# Sheet1.net
KiCad netlist of a schematic drawn in Altium Designer
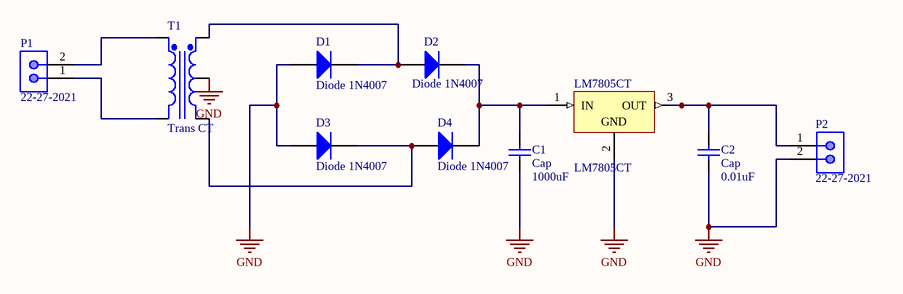
[diagram p0: Sheet1.SchDoc]

(export (version "E")
  (design (tool "Eeschema 10.0.6"))
  (components
    (comp (ref "C1")
      (value "Cap")
      (footprint "RAD-0.3")
      (description "Capacitor")
      (fields (field (name "ALTIUM_VALUE") "1000uF") (field (name "PUBLISHER") "Altium Limited"))
      (libsource (lib "Miscellaneous Devices") (part "Cap"))
    )
    (comp (ref "C2")
      (value "Cap")
      (footprint "RAD-0.3")
      (description "Capacitor")
      (fields (field (name "ALTIUM_VALUE") "0.01uF") (field (name "PUBLISHER") "Altium Limited"))
      (libsource (lib "Miscellaneous Devices") (part "Cap"))
    )
    (comp (ref "D1")
      (value "Diode 1N4007")
      (footprint "DO-41")
      (description "1 Amp General Purpose Rectifier")
      (fields (field (name "PUBLISHER") "Altium Limited"))
      (libsource (lib "Miscellaneous Devices") (part "Diode 1N4007"))
    )
    (comp (ref "D2")
      (value "Diode 1N4007")
      (footprint "DO-41")
      (description "1 Amp General Purpose Rectifier")
      (fields (field (name "PUBLISHER") "Altium Limited"))
      (libsource (lib "Miscellaneous Devices") (part "Diode 1N4007"))
    )
    (comp (ref "D3")
      (value "Diode 1N4007")
      (footprint "DO-41")
      (description "1 Amp General Purpose Rectifier")
      (fields (field (name "PUBLISHER") "Altium Limited"))
      (libsource (lib "Miscellaneous Devices") (part "Diode 1N4007"))
    )
    (comp (ref "D4")
      (value "Diode 1N4007")
      (footprint "DO-41")
      (description "1 Amp General Purpose Rectifier")
      (fields (field (name "PUBLISHER") "Altium Limited"))
      (libsource (lib "Miscellaneous Devices") (part "Diode 1N4007"))
    )
    (comp (ref "LM7805CT")
      (value "LM7805CT")
      (footprint "FAIR-TO-220-3")
      (description "Positive Voltage Regulator, 5 V, 1 A, -40 to 125 degC, 3-Pin TO-220, RoHS, Tube")
      (fields (field (name "MANUFACTURER") "FairchildSemiconductor"))
      (libsource (lib "Altium Content Vault") (part "FAIR-LM7805CT-TO220-3"))
    )
    (comp (ref "P1")
      (value "22-27-2021")
      (footprint "MOLX-22-27-2021_V")
      (fields (field (name "MANUFACTURER") "Molex") (field (name "PARTNUMBER") "0022272021"))
      (libsource (lib "") (part "CN-1P-M-R2_1"))
    )
    (comp (ref "P2")
      (value "22-27-2021")
      (footprint "MOLX-22-27-2021_V")
      (fields (field (name "MANUFACTURER") "Molex") (field (name "PARTNUMBER") "0022272021"))
      (libsource (lib "Altium Content Vault") (part "CN-1P-M-R2"))
    )
    (comp (ref "T1")
      (value "Trans CT")
      (footprint "TRF_5")
      (description "Center-Tapped Transformer (Coupled Inductor Model)")
      (fields (field (name "PUBLISHER") "Altium Limited"))
      (libsource (lib "Miscellaneous Devices") (part "Trans CT"))
    )
  )
  (nets
    (net (code "1") (name "GND") (class "Default")
      (node (ref "C1") (pin "1") (pinfunction "1_1") (pintype "passive"))
      (node (ref "C2") (pin "1") (pinfunction "1_1") (pintype "passive"))
      (node (ref "D1") (pin "1") (pinfunction "A_1") (pintype "passive"))
      (node (ref "D3") (pin "1") (pinfunction "A_1") (pintype "passive"))
      (node (ref "LM7805CT") (pin "2") (pinfunction "GND_2") (pintype "power_in"))
      (node (ref "P2") (pin "2") (pinfunction "2_2") (pintype "passive"))
      (node (ref "T1") (pin "4") (pinfunction "SecCT_4") (pintype "passive"))
    )
    (net (code "2") (name "Net-(D1-K)") (class "Default")
      (node (ref "D1") (pin "2") (pinfunction "K_2") (pintype "passive"))
      (node (ref "D2") (pin "1") (pinfunction "A_1") (pintype "passive"))
      (node (ref "T1") (pin "3") (pinfunction "Sec+_3") (pintype "passive"))
    )
    (net (code "3") (name "Net-(D2-K)") (class "Default")
      (node (ref "C1") (pin "2") (pinfunction "2_2") (pintype "passive"))
      (node (ref "D2") (pin "2") (pinfunction "K_2") (pintype "passive"))
      (node (ref "D4") (pin "2") (pinfunction "K_2") (pintype "passive"))
      (node (ref "LM7805CT") (pin "1") (pinfunction "IN_1") (pintype "input"))
    )
    (net (code "4") (name "Net-(D3-K)") (class "Default")
      (node (ref "D3") (pin "2") (pinfunction "K_2") (pintype "passive"))
      (node (ref "D4") (pin "1") (pinfunction "A_1") (pintype "passive"))
      (node (ref "T1") (pin "5") (pinfunction "Sec-_5") (pintype "passive"))
    )
    (net (code "5") (name "Net-(LM7805CT-OUT)") (class "Default")
      (node (ref "C2") (pin "2") (pinfunction "2_2") (pintype "passive"))
      (node (ref "LM7805CT") (pin "3") (pinfunction "OUT_3") (pintype "output"))
      (node (ref "P2") (pin "1") (pinfunction "1_1") (pintype "passive"))
    )
    (net (code "6") (name "Net-(T1-Pri+)") (class "Default")
      (node (ref "P1") (pin "2") (pinfunction "2_2") (pintype "passive"))
      (node (ref "T1") (pin "1") (pinfunction "Pri+_1") (pintype "passive"))
    )
    (net (code "7") (name "Net-(T1-Pri-)") (class "Default")
      (node (ref "P1") (pin "1") (pinfunction "1_1") (pintype "passive"))
      (node (ref "T1") (pin "2") (pinfunction "Pri-_2") (pintype "passive"))
    )
  )
)
